# tdr.net
KiCad netlist of a schematic drawn in EAGLE
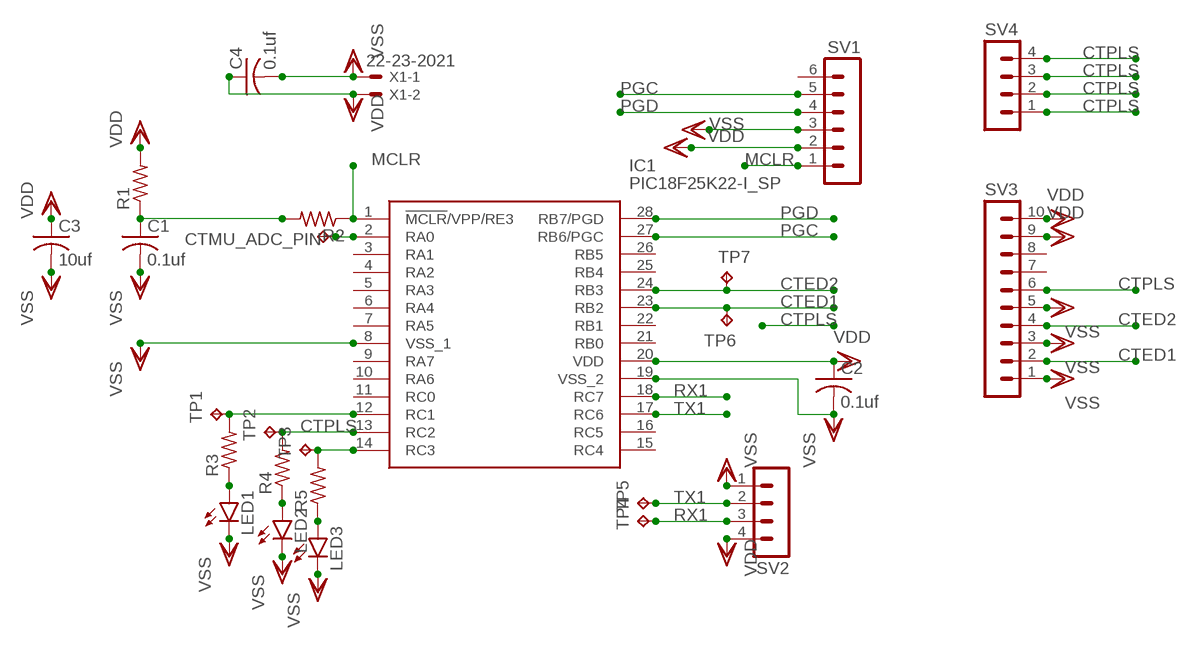
[diagram p0: schematic, sheet 1]

(export (version "E")
  (design (tool "Eeschema 10.0.6"))
  (components
    (comp (ref "C1")
      (value "0.1uf")
      (footprint "eagle-import:C0805")
      (libsource (lib "eagle-import") (part "C-USC0805"))
    )
    (comp (ref "C2")
      (value "0.1uf")
      (footprint "eagle-import:C0805")
      (libsource (lib "eagle-import") (part "C-USC0805"))
    )
    (comp (ref "C3")
      (value "10uf")
      (footprint "eagle-import:C0805")
      (libsource (lib "eagle-import") (part "C-USC0805"))
    )
    (comp (ref "C4")
      (value "0.1uf")
      (footprint "eagle-import:C0805")
      (libsource (lib "eagle-import") (part "C-USC0805"))
    )
    (comp (ref "CTMU_ADC_PIN")
      (value "TPB1,27")
      (footprint "eagle-import:B1,27")
      (libsource (lib "eagle-import") (part "TPB1,27"))
    )
    (comp (ref "IC1")
      (value "PIC18F25K22-I_SP")
      (footprint "eagle-import:DIP794W56P254L3486H508Q28N")
      (fields
        (field (name "MANUFACTURER_PART_NUMBER") "PIC18F25K22-I/SP")
        (field (name "MOUSER_PART_NUMBER") "579-PIC18F25K22ISP")
      )
      (libsource (lib "eagle-import") (part "PIC18F25K22-I_SP"))
    )
    (comp (ref "LED1")
      (value "LEDCHIP-LED0805")
      (footprint "eagle-import:CHIP-LED0805")
      (libsource (lib "eagle-import") (part "LEDCHIP-LED0805"))
    )
    (comp (ref "LED2")
      (value "LEDCHIP-LED0805")
      (footprint "eagle-import:CHIP-LED0805")
      (libsource (lib "eagle-import") (part "LEDCHIP-LED0805"))
    )
    (comp (ref "LED3")
      (value "LEDCHIP-LED0805")
      (footprint "eagle-import:CHIP-LED0805")
      (libsource (lib "eagle-import") (part "LEDCHIP-LED0805"))
    )
    (comp (ref "R1")
      (value "R-US_M0805")
      (footprint "eagle-import:M0805")
      (libsource (lib "eagle-import") (part "R-US_M0805"))
    )
    (comp (ref "R2")
      (value "R-US_M0805")
      (footprint "eagle-import:M0805")
      (libsource (lib "eagle-import") (part "R-US_M0805"))
    )
    (comp (ref "R3")
      (value "R-US_M0805")
      (footprint "eagle-import:M0805")
      (libsource (lib "eagle-import") (part "R-US_M0805"))
    )
    (comp (ref "R4")
      (value "R-US_M0805")
      (footprint "eagle-import:M0805")
      (libsource (lib "eagle-import") (part "R-US_M0805"))
    )
    (comp (ref "R5")
      (value "R-US_M0805")
      (footprint "eagle-import:M0805")
      (libsource (lib "eagle-import") (part "R-US_M0805"))
    )
    (comp (ref "SV1")
      (value "MA06-1")
      (footprint "eagle-import:MA06-1")
      (libsource (lib "eagle-import") (part "MA06-1"))
    )
    (comp (ref "SV2")
      (value "MA04-1")
      (footprint "eagle-import:MA04-1")
      (libsource (lib "eagle-import") (part "MA04-1"))
    )
    (comp (ref "SV3")
      (value "MA10-1")
      (footprint "eagle-import:MA10-1")
      (libsource (lib "eagle-import") (part "MA10-1"))
    )
    (comp (ref "SV4")
      (value "MA04-1")
      (footprint "eagle-import:MA04-1")
      (libsource (lib "eagle-import") (part "MA04-1"))
    )
    (comp (ref "TP1")
      (value "TPPAD1-13")
      (footprint "eagle-import:P1-13")
      (libsource (lib "eagle-import") (part "TPPAD1-13"))
    )
    (comp (ref "TP2")
      (value "TPPAD1-13")
      (footprint "eagle-import:P1-13")
      (libsource (lib "eagle-import") (part "TPPAD1-13"))
    )
    (comp (ref "TP3")
      (value "TPPAD1-13")
      (footprint "eagle-import:P1-13")
      (libsource (lib "eagle-import") (part "TPPAD1-13"))
    )
    (comp (ref "TP4")
      (value "TPPAD1-13")
      (footprint "eagle-import:P1-13")
      (libsource (lib "eagle-import") (part "TPPAD1-13"))
    )
    (comp (ref "TP5")
      (value "TPPAD1-13")
      (footprint "eagle-import:P1-13")
      (libsource (lib "eagle-import") (part "TPPAD1-13"))
    )
    (comp (ref "TP6")
      (value "TPPAD1-13")
      (footprint "eagle-import:P1-13")
      (libsource (lib "eagle-import") (part "TPPAD1-13"))
    )
    (comp (ref "TP7")
      (value "TPPAD1-13")
      (footprint "eagle-import:P1-13")
      (libsource (lib "eagle-import") (part "TPPAD1-13"))
    )
    (comp (ref "X1")
      (value "22-23-2021")
      (footprint "eagle-import:22-23-2021")
      (fields (field (name "MF") "MOLEX"))
      (libsource (lib "eagle-import") (part "22-23-2021"))
    )
  )
  (nets
    (net (code "1") (name "/CTED1") (class "Default")
      (node (ref "IC1") (pin "23") (pinfunction "RB2_23") (pintype "bidirectional"))
      (node (ref "SV3") (pin "2") (pinfunction "2_2") (pintype "passive"))
      (node (ref "TP6") (pin "TP") (pinfunction "TP_TP") (pintype "input"))
    )
    (net (code "2") (name "/CTED2") (class "Default")
      (node (ref "IC1") (pin "24") (pinfunction "RB3_24") (pintype "bidirectional"))
      (node (ref "SV3") (pin "4") (pinfunction "4_4") (pintype "passive"))
      (node (ref "TP7") (pin "TP") (pinfunction "TP_TP") (pintype "input"))
    )
    (net (code "3") (name "/CTPLS") (class "Default")
      (node (ref "IC1") (pin "13") (pinfunction "RC2_13") (pintype "bidirectional"))
      (node (ref "R4") (pin "2") (pinfunction "2_2") (pintype "passive"))
      (node (ref "SV3") (pin "6") (pinfunction "6_6") (pintype "passive"))
      (node (ref "SV4") (pin "1") (pinfunction "1_1") (pintype "passive"))
      (node (ref "SV4") (pin "2") (pinfunction "2_2") (pintype "passive"))
      (node (ref "SV4") (pin "3") (pinfunction "3_3") (pintype "passive"))
      (node (ref "SV4") (pin "4") (pinfunction "4_4") (pintype "passive"))
      (node (ref "TP2") (pin "TP") (pinfunction "TP_TP") (pintype "input"))
    )
    (net (code "4") (name "/MCLR") (class "Default")
      (node (ref "IC1") (pin "1") (pinfunction "~{MCLR}/VPP/RE3_1") (pintype "bidirectional"))
      (node (ref "R2") (pin "1") (pinfunction "1_1") (pintype "passive"))
      (node (ref "SV1") (pin "1") (pinfunction "1_1") (pintype "passive"))
    )
    (net (code "5") (name "/PGC") (class "Default")
      (node (ref "IC1") (pin "27") (pinfunction "RB6/PGC_27") (pintype "bidirectional"))
      (node (ref "SV1") (pin "5") (pinfunction "5_5") (pintype "passive"))
    )
    (net (code "6") (name "/PGD") (class "Default")
      (node (ref "IC1") (pin "28") (pinfunction "RB7/PGD_28") (pintype "bidirectional"))
      (node (ref "SV1") (pin "4") (pinfunction "4_4") (pintype "passive"))
    )
    (net (code "7") (name "/RX1") (class "Default")
      (node (ref "IC1") (pin "18") (pinfunction "RC7_18") (pintype "bidirectional"))
      (node (ref "SV2") (pin "3") (pinfunction "3_3") (pintype "passive"))
      (node (ref "TP4") (pin "TP") (pinfunction "TP_TP") (pintype "input"))
    )
    (net (code "8") (name "/TX1") (class "Default")
      (node (ref "IC1") (pin "17") (pinfunction "RC6_17") (pintype "bidirectional"))
      (node (ref "SV2") (pin "2") (pinfunction "2_2") (pintype "passive"))
      (node (ref "TP5") (pin "TP") (pinfunction "TP_TP") (pintype "input"))
    )
    (net (code "9") (name "Net-(C1-Pad1)") (class "Default")
      (node (ref "C1") (pin "1") (pinfunction "1_1") (pintype "passive"))
      (node (ref "R1") (pin "1") (pinfunction "1_1") (pintype "passive"))
      (node (ref "R2") (pin "2") (pinfunction "2_2") (pintype "passive"))
    )
    (net (code "10") (name "Net-(IC1-RA0)") (class "Default")
      (node (ref "CTMU_ADC_PIN") (pin "TP") (pinfunction "TP_TP") (pintype "input"))
      (node (ref "IC1") (pin "2") (pinfunction "RA0_2") (pintype "bidirectional"))
    )
    (net (code "11") (name "Net-(IC1-RC1)") (class "Default")
      (node (ref "IC1") (pin "12") (pinfunction "RC1_12") (pintype "bidirectional"))
      (node (ref "R3") (pin "2") (pinfunction "2_2") (pintype "passive"))
      (node (ref "TP1") (pin "TP") (pinfunction "TP_TP") (pintype "input"))
    )
    (net (code "12") (name "Net-(IC1-RC3)") (class "Default")
      (node (ref "IC1") (pin "14") (pinfunction "RC3_14") (pintype "bidirectional"))
      (node (ref "R5") (pin "2") (pinfunction "2_2") (pintype "passive"))
      (node (ref "TP3") (pin "TP") (pinfunction "TP_TP") (pintype "input"))
    )
    (net (code "13") (name "Net-(LED1-PadA)") (class "Default")
      (node (ref "LED1") (pin "A") (pinfunction "A_A") (pintype "passive"))
      (node (ref "R3") (pin "1") (pinfunction "1_1") (pintype "passive"))
    )
    (net (code "14") (name "Net-(LED2-PadA)") (class "Default")
      (node (ref "LED2") (pin "A") (pinfunction "A_A") (pintype "passive"))
      (node (ref "R4") (pin "1") (pinfunction "1_1") (pintype "passive"))
    )
    (net (code "15") (name "Net-(LED3-PadA)") (class "Default")
      (node (ref "LED3") (pin "A") (pinfunction "A_A") (pintype "passive"))
      (node (ref "R5") (pin "1") (pinfunction "1_1") (pintype "passive"))
    )
    (net (code "16") (name "VDD") (class "Default")
      (node (ref "C2") (pin "1") (pinfunction "1_1") (pintype "passive"))
      (node (ref "C3") (pin "1") (pinfunction "1_1") (pintype "passive"))
      (node (ref "C4") (pin "1") (pinfunction "1_1") (pintype "passive"))
      (node (ref "IC1") (pin "20") (pinfunction "VDD_20") (pintype "bidirectional"))
      (node (ref "R1") (pin "2") (pinfunction "2_2") (pintype "passive"))
      (node (ref "SV1") (pin "2") (pinfunction "2_2") (pintype "passive"))
      (node (ref "SV2") (pin "4") (pinfunction "4_4") (pintype "passive"))
      (node (ref "SV3") (pin "10") (pinfunction "10_10") (pintype "passive"))
      (node (ref "SV3") (pin "9") (pinfunction "9_9") (pintype "passive"))
      (node (ref "X1") (pin "2") (pinfunction "S_2") (pintype "passive"))
    )
    (net (code "17") (name "VSS") (class "Default")
      (node (ref "C1") (pin "2") (pinfunction "2_2") (pintype "passive"))
      (node (ref "C2") (pin "2") (pinfunction "2_2") (pintype "passive"))
      (node (ref "C3") (pin "2") (pinfunction "2_2") (pintype "passive"))
      (node (ref "C4") (pin "2") (pinfunction "2_2") (pintype "passive"))
      (node (ref "IC1") (pin "19") (pinfunction "VSS_2_19") (pintype "bidirectional"))
      (node (ref "IC1") (pin "8") (pinfunction "VSS_1_8") (pintype "bidirectional"))
      (node (ref "LED1") (pin "C") (pinfunction "C_C") (pintype "passive"))
      (node (ref "LED2") (pin "C") (pinfunction "C_C") (pintype "passive"))
      (node (ref "LED3") (pin "C") (pinfunction "C_C") (pintype "passive"))
      (node (ref "SV1") (pin "3") (pinfunction "3_3") (pintype "passive"))
      (node (ref "SV2") (pin "1") (pinfunction "1_1") (pintype "passive"))
      (node (ref "SV3") (pin "1") (pinfunction "1_1") (pintype "passive"))
      (node (ref "SV3") (pin "3") (pinfunction "3_3") (pintype "passive"))
      (node (ref "SV3") (pin "5") (pinfunction "5_5") (pintype "passive"))
      (node (ref "X1") (pin "1") (pinfunction "S_1") (pintype "passive"))
    )
    (net (code "18") (name "unconnected-(IC1-RA1-Pad3)") (class "Default")
      (node (ref "IC1") (pin "3") (pinfunction "RA1_3") (pintype "bidirectional"))
    )
    (net (code "19") (name "unconnected-(IC1-RA2-Pad4)") (class "Default")
      (node (ref "IC1") (pin "4") (pinfunction "RA2_4") (pintype "bidirectional"))
    )
    (net (code "20") (name "unconnected-(IC1-RA3-Pad5)") (class "Default")
      (node (ref "IC1") (pin "5") (pinfunction "RA3_5") (pintype "bidirectional"))
    )
    (net (code "21") (name "unconnected-(IC1-RA4-Pad6)") (class "Default")
      (node (ref "IC1") (pin "6") (pinfunction "RA4_6") (pintype "bidirectional"))
    )
    (net (code "22") (name "unconnected-(IC1-RA5-Pad7)") (class "Default")
      (node (ref "IC1") (pin "7") (pinfunction "RA5_7") (pintype "bidirectional"))
    )
    (net (code "23") (name "unconnected-(IC1-RA6-Pad10)") (class "Default")
      (node (ref "IC1") (pin "10") (pinfunction "RA6_10") (pintype "bidirectional"))
    )
    (net (code "24") (name "unconnected-(IC1-RA7-Pad9)") (class "Default")
      (node (ref "IC1") (pin "9") (pinfunction "RA7_9") (pintype "bidirectional"))
    )
    (net (code "25") (name "unconnected-(IC1-RB0-Pad21)") (class "Default")
      (node (ref "IC1") (pin "21") (pinfunction "RB0_21") (pintype "bidirectional"))
    )
    (net (code "26") (name "unconnected-(IC1-RB1-Pad22)") (class "Default")
      (node (ref "IC1") (pin "22") (pinfunction "RB1_22") (pintype "bidirectional"))
    )
    (net (code "27") (name "unconnected-(IC1-RB4-Pad25)") (class "Default")
      (node (ref "IC1") (pin "25") (pinfunction "RB4_25") (pintype "bidirectional"))
    )
    (net (code "28") (name "unconnected-(IC1-RB5-Pad26)") (class "Default")
      (node (ref "IC1") (pin "26") (pinfunction "RB5_26") (pintype "bidirectional"))
    )
    (net (code "29") (name "unconnected-(IC1-RC0-Pad11)") (class "Default")
      (node (ref "IC1") (pin "11") (pinfunction "RC0_11") (pintype "bidirectional"))
    )
    (net (code "30") (name "unconnected-(IC1-RC4-Pad15)") (class "Default")
      (node (ref "IC1") (pin "15") (pinfunction "RC4_15") (pintype "bidirectional"))
    )
    (net (code "31") (name "unconnected-(IC1-RC5-Pad16)") (class "Default")
      (node (ref "IC1") (pin "16") (pinfunction "RC5_16") (pintype "bidirectional"))
    )
    (net (code "32") (name "unconnected-(SV1-Pad6)") (class "Default")
      (node (ref "SV1") (pin "6") (pinfunction "6_6") (pintype "passive"))
    )
    (net (code "33") (name "unconnected-(SV3-Pad7)") (class "Default")
      (node (ref "SV3") (pin "7") (pinfunction "7_7") (pintype "passive"))
    )
    (net (code "34") (name "unconnected-(SV3-Pad8)") (class "Default")
      (node (ref "SV3") (pin "8") (pinfunction "8_8") (pintype "passive"))
    )
  )
)
